# parent_easyeda.net
KiCad netlist of a schematic drawn in EasyEDA
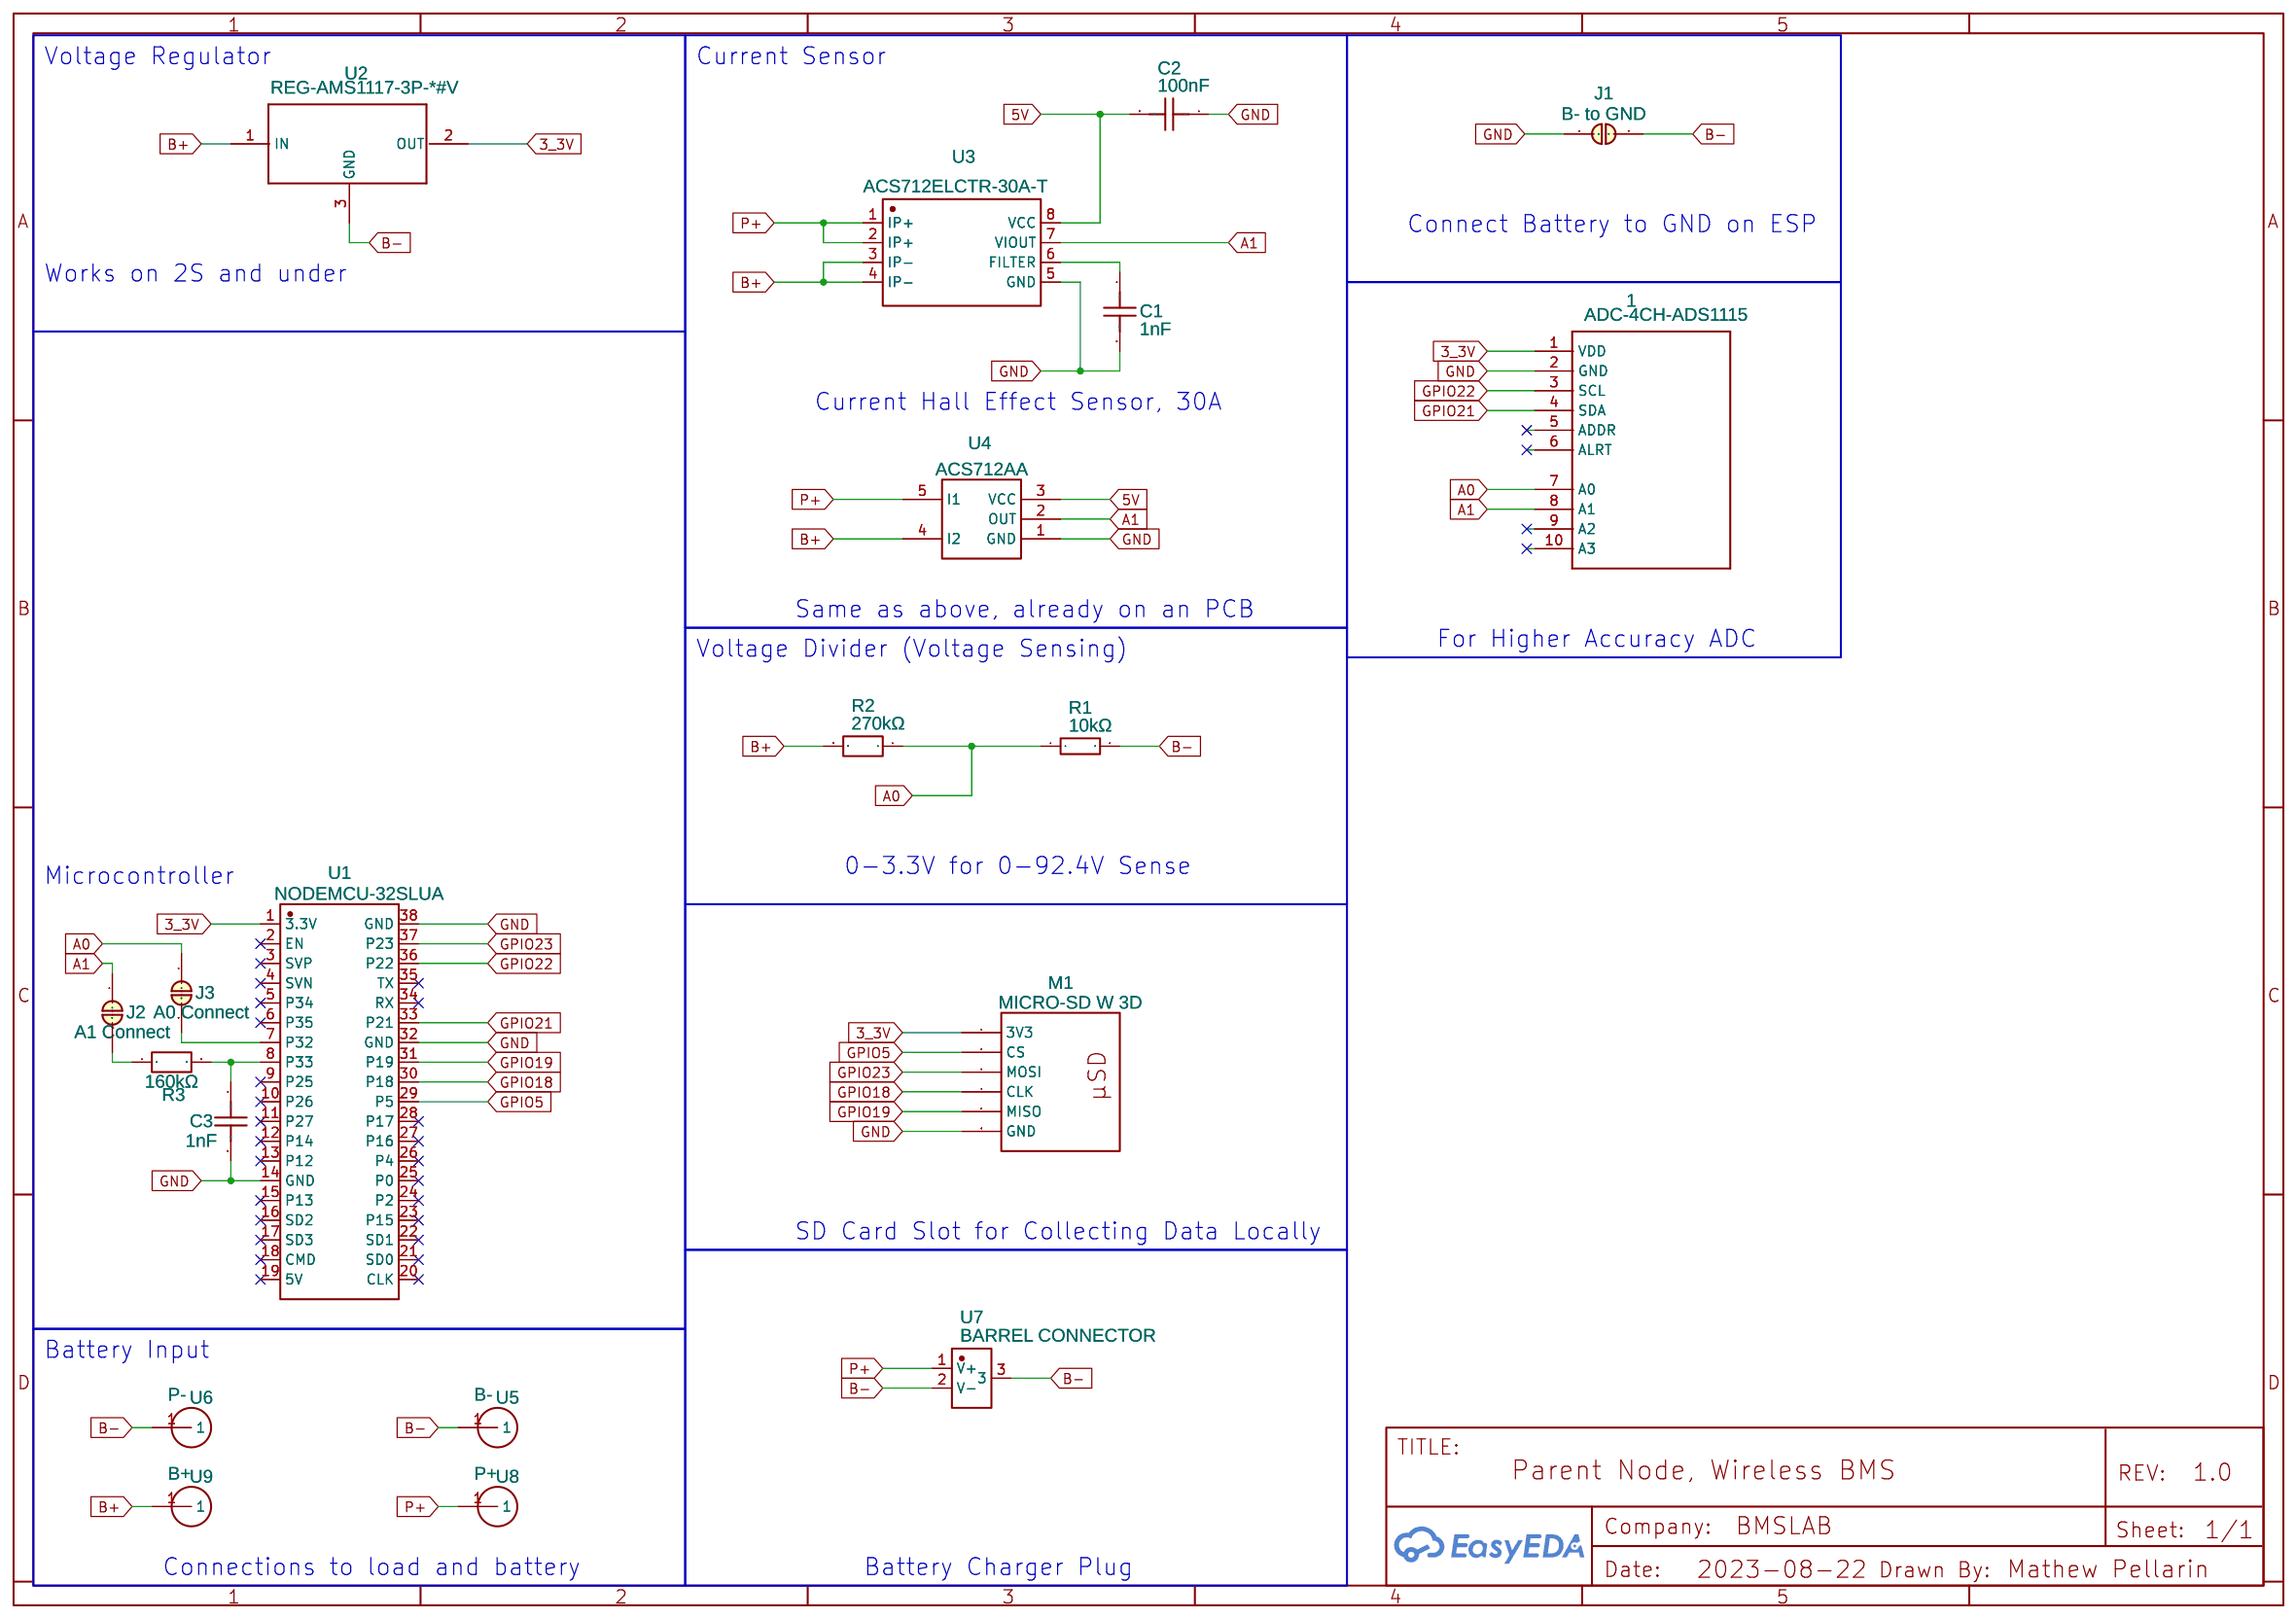
[diagram p0: schematic sheet]

(export (version "E")
  (design (tool "Eeschema 10.0.6"))
  (components
    (comp (ref "1") (value "ADC-4CH-ADS1115") (libsource (lib "") (part "ADC-4CH-ADS1115")))
    (comp (ref "C1")
      (value "1nF")
      (fields
        (field (name "Manufacturer Part") "Y5P102K2KV16CC0224")
        (field (name "Manufacturer") "KNSCHA(科尼盛)")
      )
      (libsource (lib "") (part "Y5P102K2KV16CC0224"))
    )
    (comp (ref "C2")
      (value "100nF")
      (fields
        (field (name "Manufacturer Part") "CC1H104ZA1PD3F5O30MF")
        (field (name "Manufacturer") "Dersonic(德尔创)")
      )
      (libsource (lib "") (part "CC1H104ZA1PD3F5O30MF"))
    )
    (comp (ref "C3")
      (value "1nF")
      (fields
        (field (name "Manufacturer Part") "Y5P102K2KV16CC0224")
        (field (name "Manufacturer") "KNSCHA(科尼盛)")
      )
      (libsource (lib "") (part "Y5P102K2KV16CC0224"))
    )
    (comp (ref "J1") (value "B- to GND") (libsource (lib "") (part "SOLDERJUMPERSMALL")))
    (comp (ref "J2") (value "A1 Connect") (libsource (lib "") (part "SOLDERJUMPERSMALL_1")))
    (comp (ref "J3") (value "A0 Connect") (libsource (lib "") (part "SOLDERJUMPERSMALL_1")))
    (comp (ref "M1") (value "MICRO-SD W 3D") (libsource (lib "") (part "MICRO-SD W 3D")))
    (comp (ref "R1")
      (value "10kΩ")
      (fields (field (name "Manufacturer Part") "MFR-25FTE52-100K") (field (name "Manufacturer") "YAGEO(国巨)"))
      (libsource (lib "") (part "MFR-25FTE52-100K"))
    )
    (comp (ref "R2")
      (value "270kΩ")
      (fields (field (name "Manufacturer Part") "CFR-25JR-52-270K") (field (name "Manufacturer") "YAGEO(国巨)"))
      (libsource (lib "") (part "CFR-25JR-52-270K_1"))
    )
    (comp (ref "R3")
      (value "160kΩ")
      (fields (field (name "Manufacturer Part") "CFR-25JR-52-270K") (field (name "Manufacturer") "YAGEO(国巨)"))
      (libsource (lib "") (part "CFR-25JR-52-270K"))
    )
    (comp (ref "U1")
      (value "NODEMCU-32SLUA")
      (fields
        (field (name "Manufacturer Part") "NodeMCU-32SLua")
        (field (name "Manufacturer") "Ai-Thinker(安信可)")
      )
      (libsource (lib "") (part "NODEMCU-32SLUA"))
    )
    (comp (ref "U2") (value "REG-AMS1117-3P-*#V") (libsource (lib "") (part "REG-AMS1117-3P-*#V")))
    (comp (ref "U3")
      (value "ACS712ELCTR-30A-T")
      (fields (field (name "Manufacturer") "ALLEGRO(美国埃戈罗)"))
      (libsource (lib "") (part "ACS712ELCTR-30A-T"))
    )
    (comp (ref "U4") (value "ACS712AA") (libsource (lib "") (part "ACS712AA")))
    (comp (ref "U5") (value "B-") (libsource (lib "") (part "13-GAUGE")))
    (comp (ref "U6") (value "P-") (libsource (lib "") (part "13-GAUGE")))
    (comp (ref "U7") (value "BARREL CONNECTOR") (libsource (lib "") (part "BARREL CONNECTOR")))
    (comp (ref "U8") (value "P+") (libsource (lib "") (part "13-GAUGE")))
    (comp (ref "U9") (value "B+") (libsource (lib "") (part "13-GAUGE")))
  )
  (nets
    (net (code "1") (name "3_3V") (class "Default")
      (node (ref "1") (pin "1") (pinfunction "VDD_1") (pintype "bidirectional"))
      (node (ref "M1") (pin "1") (pinfunction "3V3_1") (pintype "unspecified"))
      (node (ref "U1") (pin "1") (pinfunction "3.3V_1") (pintype "unspecified"))
      (node (ref "U2") (pin "2") (pinfunction "OUT_2") (pintype "bidirectional"))
    )
    (net (code "2") (name "5V") (class "Default")
      (node (ref "C2") (pin "2") (pinfunction "2_2") (pintype "unspecified"))
      (node (ref "U3") (pin "8") (pinfunction "VCC_8") (pintype "unspecified"))
      (node (ref "U4") (pin "3") (pinfunction "VCC_3") (pintype "unspecified"))
    )
    (net (code "3") (name "A0") (class "Default")
      (node (ref "1") (pin "7") (pinfunction "A0_7") (pintype "bidirectional"))
      (node (ref "J3") (pin "1") (pinfunction "1_1") (pintype "unspecified"))
      (node (ref "R1") (pin "1") (pinfunction "1_1") (pintype "unspecified"))
      (node (ref "R2") (pin "1") (pinfunction "1_1") (pintype "unspecified"))
    )
    (net (code "4") (name "A1") (class "Default")
      (node (ref "1") (pin "8") (pinfunction "A1_8") (pintype "bidirectional"))
      (node (ref "J2") (pin "1") (pinfunction "1_1") (pintype "unspecified"))
      (node (ref "U3") (pin "7") (pinfunction "VIOUT_7") (pintype "unspecified"))
      (node (ref "U4") (pin "2") (pinfunction "OUT_2") (pintype "unspecified"))
    )
    (net (code "5") (name "B+") (class "Default")
      (node (ref "R2") (pin "2") (pinfunction "2_2") (pintype "unspecified"))
      (node (ref "U2") (pin "1") (pinfunction "IN_1") (pintype "bidirectional"))
      (node (ref "U3") (pin "3") (pinfunction "IP-_3") (pintype "unspecified"))
      (node (ref "U3") (pin "4") (pinfunction "IP-_4") (pintype "unspecified"))
      (node (ref "U4") (pin "4") (pinfunction "I2_4") (pintype "unspecified"))
      (node (ref "U9") (pin "1") (pinfunction "1_1") (pintype "unspecified"))
    )
    (net (code "6") (name "B-") (class "Default")
      (node (ref "J1") (pin "2") (pinfunction "2_2") (pintype "unspecified"))
      (node (ref "R1") (pin "2") (pinfunction "2_2") (pintype "unspecified"))
      (node (ref "U2") (pin "3") (pinfunction "GND_3") (pintype "bidirectional"))
      (node (ref "U5") (pin "1") (pinfunction "1_1") (pintype "unspecified"))
      (node (ref "U6") (pin "1") (pinfunction "1_1") (pintype "unspecified"))
      (node (ref "U7") (pin "2") (pinfunction "V-_2") (pintype "unspecified"))
      (node (ref "U7") (pin "3") (pinfunction "3_3") (pintype "unspecified"))
    )
    (net (code "7") (name "GND") (class "Default")
      (node (ref "1") (pin "2") (pinfunction "GND_2") (pintype "bidirectional"))
      (node (ref "C1") (pin "2") (pinfunction "2_2") (pintype "unspecified"))
      (node (ref "C2") (pin "1") (pinfunction "1_1") (pintype "unspecified"))
      (node (ref "C3") (pin "2") (pinfunction "2_2") (pintype "unspecified"))
      (node (ref "J1") (pin "1") (pinfunction "1_1") (pintype "unspecified"))
      (node (ref "M1") (pin "6") (pinfunction "GND_6") (pintype "unspecified"))
      (node (ref "U1") (pin "14") (pinfunction "GND_14") (pintype "unspecified"))
      (node (ref "U1") (pin "32") (pinfunction "GND_32") (pintype "unspecified"))
      (node (ref "U1") (pin "38") (pinfunction "GND_38") (pintype "unspecified"))
      (node (ref "U3") (pin "5") (pinfunction "GND_5") (pintype "unspecified"))
      (node (ref "U4") (pin "1") (pinfunction "GND_1") (pintype "unspecified"))
    )
    (net (code "8") (name "GPIO5") (class "Default")
      (node (ref "M1") (pin "2") (pinfunction "CS_2") (pintype "unspecified"))
      (node (ref "U1") (pin "29") (pinfunction "P5_29") (pintype "unspecified"))
    )
    (net (code "9") (name "GPIO18") (class "Default")
      (node (ref "M1") (pin "4") (pinfunction "CLK_4") (pintype "unspecified"))
      (node (ref "U1") (pin "30") (pinfunction "P18_30") (pintype "unspecified"))
    )
    (net (code "10") (name "GPIO19") (class "Default")
      (node (ref "M1") (pin "5") (pinfunction "MISO_5") (pintype "unspecified"))
      (node (ref "U1") (pin "31") (pinfunction "P19_31") (pintype "unspecified"))
    )
    (net (code "11") (name "GPIO21") (class "Default")
      (node (ref "1") (pin "4") (pinfunction "SDA_4") (pintype "bidirectional"))
      (node (ref "U1") (pin "33") (pinfunction "P21_33") (pintype "unspecified"))
    )
    (net (code "12") (name "GPIO22") (class "Default")
      (node (ref "1") (pin "3") (pinfunction "SCL_3") (pintype "bidirectional"))
      (node (ref "U1") (pin "36") (pinfunction "P22_36") (pintype "unspecified"))
    )
    (net (code "13") (name "GPIO23") (class "Default")
      (node (ref "M1") (pin "3") (pinfunction "MOSI_3") (pintype "unspecified"))
      (node (ref "U1") (pin "37") (pinfunction "P23_37") (pintype "unspecified"))
    )
    (net (code "14") (name "Net-(J2-Pad2)") (class "Default")
      (node (ref "J2") (pin "2") (pinfunction "2_2") (pintype "unspecified"))
      (node (ref "R3") (pin "1") (pinfunction "1_1") (pintype "unspecified"))
    )
    (net (code "15") (name "Net-(U1-P32)") (class "Default")
      (node (ref "J3") (pin "2") (pinfunction "2_2") (pintype "unspecified"))
      (node (ref "U1") (pin "7") (pinfunction "P32_7") (pintype "unspecified"))
    )
    (net (code "16") (name "Net-(U1-P33)") (class "Default")
      (node (ref "C3") (pin "1") (pinfunction "1_1") (pintype "unspecified"))
      (node (ref "R3") (pin "2") (pinfunction "2_2") (pintype "unspecified"))
      (node (ref "U1") (pin "8") (pinfunction "P33_8") (pintype "unspecified"))
    )
    (net (code "17") (name "Net-(U3-FILTER)") (class "Default")
      (node (ref "C1") (pin "1") (pinfunction "1_1") (pintype "unspecified"))
      (node (ref "U3") (pin "6") (pinfunction "FILTER_6") (pintype "unspecified"))
    )
    (net (code "18") (name "P+") (class "Default")
      (node (ref "U3") (pin "1") (pinfunction "IP+_1") (pintype "unspecified"))
      (node (ref "U3") (pin "2") (pinfunction "IP+_2") (pintype "unspecified"))
      (node (ref "U4") (pin "5") (pinfunction "I1_5") (pintype "unspecified"))
      (node (ref "U7") (pin "1") (pinfunction "V+_1") (pintype "unspecified"))
      (node (ref "U8") (pin "1") (pinfunction "1_1") (pintype "unspecified"))
    )
    (net (code "19") (name "unconnected-(1-A2-Pad9)") (class "Default")
      (node (ref "1") (pin "9") (pinfunction "A2_9") (pintype "bidirectional+no_connect"))
    )
    (net (code "20") (name "unconnected-(1-A3-Pad10)") (class "Default")
      (node (ref "1") (pin "10") (pinfunction "A3_10") (pintype "bidirectional+no_connect"))
    )
    (net (code "21") (name "unconnected-(1-ADDR-Pad5)") (class "Default")
      (node (ref "1") (pin "5") (pinfunction "ADDR_5") (pintype "bidirectional+no_connect"))
    )
    (net (code "22") (name "unconnected-(1-ALRT-Pad6)") (class "Default")
      (node (ref "1") (pin "6") (pinfunction "ALRT_6") (pintype "bidirectional+no_connect"))
    )
    (net (code "23") (name "unconnected-(U1-5V-Pad19)") (class "Default")
      (node (ref "U1") (pin "19") (pinfunction "5V_19") (pintype "unspecified+no_connect"))
    )
    (net (code "24") (name "unconnected-(U1-CLK-Pad20)") (class "Default")
      (node (ref "U1") (pin "20") (pinfunction "CLK_20") (pintype "unspecified+no_connect"))
    )
    (net (code "25") (name "unconnected-(U1-CMD-Pad18)") (class "Default")
      (node (ref "U1") (pin "18") (pinfunction "CMD_18") (pintype "unspecified+no_connect"))
    )
    (net (code "26") (name "unconnected-(U1-EN-Pad2)") (class "Default")
      (node (ref "U1") (pin "2") (pinfunction "EN_2") (pintype "unspecified+no_connect"))
    )
    (net (code "27") (name "unconnected-(U1-P0-Pad25)") (class "Default")
      (node (ref "U1") (pin "25") (pinfunction "P0_25") (pintype "unspecified+no_connect"))
    )
    (net (code "28") (name "unconnected-(U1-P2-Pad24)") (class "Default")
      (node (ref "U1") (pin "24") (pinfunction "P2_24") (pintype "unspecified+no_connect"))
    )
    (net (code "29") (name "unconnected-(U1-P4-Pad26)") (class "Default")
      (node (ref "U1") (pin "26") (pinfunction "P4_26") (pintype "unspecified+no_connect"))
    )
    (net (code "30") (name "unconnected-(U1-P12-Pad13)") (class "Default")
      (node (ref "U1") (pin "13") (pinfunction "P12_13") (pintype "unspecified+no_connect"))
    )
    (net (code "31") (name "unconnected-(U1-P13-Pad15)") (class "Default")
      (node (ref "U1") (pin "15") (pinfunction "P13_15") (pintype "unspecified+no_connect"))
    )
    (net (code "32") (name "unconnected-(U1-P14-Pad12)") (class "Default")
      (node (ref "U1") (pin "12") (pinfunction "P14_12") (pintype "unspecified+no_connect"))
    )
    (net (code "33") (name "unconnected-(U1-P15-Pad23)") (class "Default")
      (node (ref "U1") (pin "23") (pinfunction "P15_23") (pintype "unspecified+no_connect"))
    )
    (net (code "34") (name "unconnected-(U1-P16-Pad27)") (class "Default")
      (node (ref "U1") (pin "27") (pinfunction "P16_27") (pintype "unspecified+no_connect"))
    )
    (net (code "35") (name "unconnected-(U1-P17-Pad28)") (class "Default")
      (node (ref "U1") (pin "28") (pinfunction "P17_28") (pintype "unspecified+no_connect"))
    )
    (net (code "36") (name "unconnected-(U1-P25-Pad9)") (class "Default")
      (node (ref "U1") (pin "9") (pinfunction "P25_9") (pintype "unspecified+no_connect"))
    )
    (net (code "37") (name "unconnected-(U1-P26-Pad10)") (class "Default")
      (node (ref "U1") (pin "10") (pinfunction "P26_10") (pintype "unspecified+no_connect"))
    )
    (net (code "38") (name "unconnected-(U1-P27-Pad11)") (class "Default")
      (node (ref "U1") (pin "11") (pinfunction "P27_11") (pintype "unspecified+no_connect"))
    )
    (net (code "39") (name "unconnected-(U1-P34-Pad5)") (class "Default")
      (node (ref "U1") (pin "5") (pinfunction "P34_5") (pintype "unspecified+no_connect"))
    )
    (net (code "40") (name "unconnected-(U1-P35-Pad6)") (class "Default")
      (node (ref "U1") (pin "6") (pinfunction "P35_6") (pintype "unspecified+no_connect"))
    )
    (net (code "41") (name "unconnected-(U1-RX-Pad34)") (class "Default")
      (node (ref "U1") (pin "34") (pinfunction "RX_34") (pintype "unspecified+no_connect"))
    )
    (net (code "42") (name "unconnected-(U1-SD0-Pad21)") (class "Default")
      (node (ref "U1") (pin "21") (pinfunction "SD0_21") (pintype "unspecified+no_connect"))
    )
    (net (code "43") (name "unconnected-(U1-SD1-Pad22)") (class "Default")
      (node (ref "U1") (pin "22") (pinfunction "SD1_22") (pintype "unspecified+no_connect"))
    )
    (net (code "44") (name "unconnected-(U1-SD2-Pad16)") (class "Default")
      (node (ref "U1") (pin "16") (pinfunction "SD2_16") (pintype "unspecified+no_connect"))
    )
    (net (code "45") (name "unconnected-(U1-SD3-Pad17)") (class "Default")
      (node (ref "U1") (pin "17") (pinfunction "SD3_17") (pintype "unspecified+no_connect"))
    )
    (net (code "46") (name "unconnected-(U1-SVN-Pad4)") (class "Default")
      (node (ref "U1") (pin "4") (pinfunction "SVN_4") (pintype "unspecified+no_connect"))
    )
    (net (code "47") (name "unconnected-(U1-SVP-Pad3)") (class "Default")
      (node (ref "U1") (pin "3") (pinfunction "SVP_3") (pintype "unspecified+no_connect"))
    )
    (net (code "48") (name "unconnected-(U1-TX-Pad35)") (class "Default")
      (node (ref "U1") (pin "35") (pinfunction "TX_35") (pintype "unspecified+no_connect"))
    )
  )
)
